# OCP.net
KiCad netlist of a schematic drawn in Altium Designer
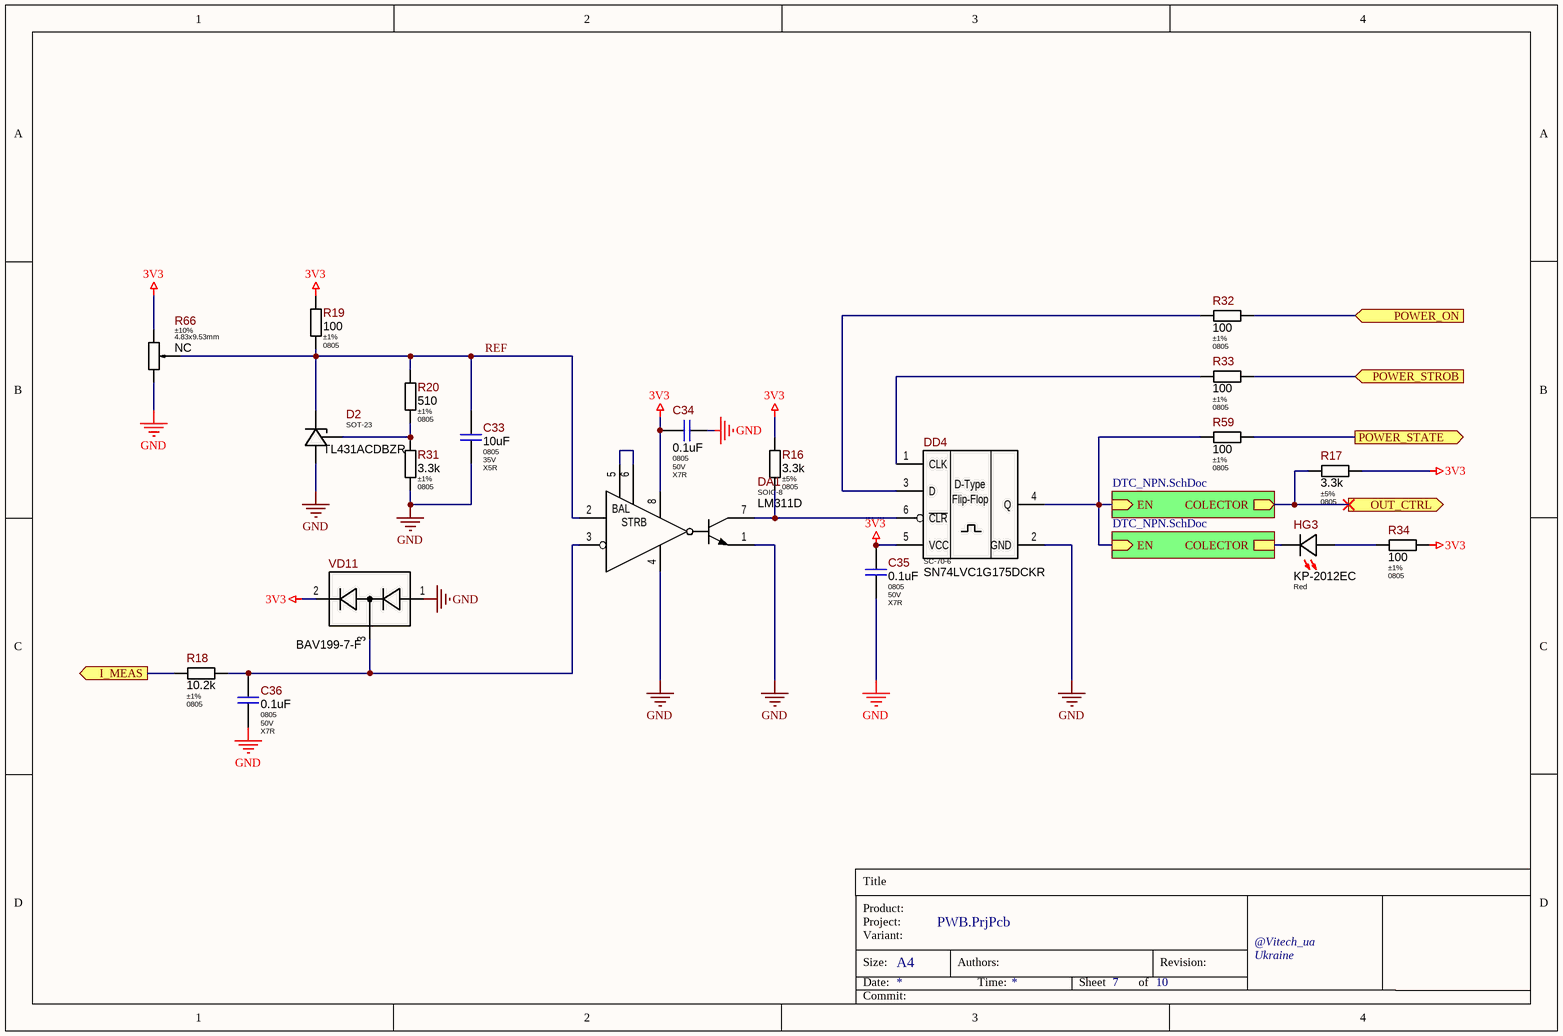
[diagram p0: OCP.SchDoc]

(export (version "E")
  (design (tool "Eeschema 10.0.6"))
  (components
    (comp (ref "C33")
      (value "10uF")
      (footprint "CAP-0805(2012)X125T20")
      (description "10uF 35V X5R ±10% 0805 Low ESL Ceramic Capacitor RoHS")
      (fields
        (field (name "PACKAGE") "0805")
        (field (name "VOLTAGE") "35V")
        (field (name "DIELECTRIC TYPE") "X5R")
        (field (name "PART NUMBER") "C2012X5R1V106K125AC")
        (field (name "MANUFACTURER") "TDK Corporation")
      )
      (libsource (lib "capacitors") (part "C2012X5R1V106K125AC"))
    )
    (comp (ref "C34")
      (value "0.1uF")
      (footprint "CAP-0805(2012)X85T10")
      (description "100nF 50V X7R ±10% 0805 Ceramic Capacitor RoHS")
      (fields
        (field (name "PACKAGE") "0805")
        (field (name "VOLTAGE") "50V")
        (field (name "DIELECTRIC TYPE") "X7R")
        (field (name "PART NUMBER") "CL21B104KBCNNNC")
        (field (name "MANUFACTURER") "Samsung Electro-Mechanics")
      )
      (libsource (lib "capacitors") (part "CL21B104KBCNNNC"))
    )
    (comp (ref "C35")
      (value "0.1uF")
      (footprint "CAP-0805(2012)X85T10")
      (description "100nF 50V X7R ±10% 0805 Ceramic Capacitor RoHS")
      (fields
        (field (name "PACKAGE") "0805")
        (field (name "VOLTAGE") "50V")
        (field (name "DIELECTRIC TYPE") "X7R")
        (field (name "PART NUMBER") "CL21B104KBCNNNC")
        (field (name "MANUFACTURER") "Samsung Electro-Mechanics")
      )
      (libsource (lib "capacitors") (part "CL21B104KBCNNNC"))
    )
    (comp (ref "C36")
      (value "0.1uF")
      (footprint "CAP-0805(2012)X85T10")
      (description "100nF 50V X7R ±10% 0805 Ceramic Capacitor RoHS")
      (fields
        (field (name "PACKAGE") "0805")
        (field (name "VOLTAGE") "50V")
        (field (name "DIELECTRIC TYPE") "X7R")
        (field (name "PART NUMBER") "CL21B104KBCNNNC")
        (field (name "MANUFACTURER") "Samsung Electro-Mechanics")
      )
      (libsource (lib "capacitors") (part "CL21B104KBCNNNC"))
    )
    (comp (ref "D2")
      (value "TL431ACDBZR")
      (footprint "SOT-23_MED")
      (description "Adjustable Precision Shunt Regulator, Accuracy 1%,  SOT-23-3")
      (fields
        (field (name "PACKAGE") "SOT-23")
        (field (name "PART NUMBER") "TL431ACDBZR")
        (field (name "MANUFACTURER") "Texas Instruments")
      )
      (libsource (lib "ic") (part "TL431ACDBZR"))
    )
    (comp (ref "DA1")
      (value "LM311D")
      (footprint "SOIC-8_W3.9MM")
      (description "Differential General Purpose Comparator with Open-Collector, Open-Emitter, SOIC-8")
      (fields
        (field (name "PACKAGE") "SOIC-8")
        (field (name "PART NUMBER") "LM311D")
        (field (name "MANUFACTURER") "Texas Instruments")
      )
      (libsource (lib "ic") (part "LM311D"))
    )
    (comp (ref "DD4")
      (value "SN74LVC1G175DCKR")
      (footprint "SC-70-6")
      (description "Single D-type Flip-Flop with Asynchronous Clear, Positive Edge Trigger, SC-70-6")
      (fields
        (field (name "PACKAGE") "SC-70-6")
        (field (name "PART NUMBER") "SN74LVC1G175DCKR")
        (field (name "MANUFACTURER") "Texas Instruments")
      )
      (libsource (lib "ic") (part "SN74LVC1G175DCKR"))
    )
    (comp (ref "HG3")
      (value "KP-2012EC")
      (footprint "KP-2012EC")
      (description "Low Power LED, Red 617nm, SMD, Vf 2V, 15mcd @ 20 mA, 160°")
      (fields
        (field (name "PART NUMBER") "KP-2012EC")
        (field (name "COLOR") "Red")
        (field (name "MANUFACTURER") "Kingbright")
      )
      (libsource (lib "opto") (part "KP-2012EC"))
    )
    (comp (ref "R16")
      (value "3.3k")
      (footprint "R_ANY_CHIP_0805_MED")
      (description "3.3 kOhms ±5%, 1/8W 0805 Thick Film Resistor")
      (fields
        (field (name "TOLERANCE") "±5%")
        (field (name "PACKAGE") "0805")
        (field (name "PART NUMBER") "RC0805JR-073K3L")
        (field (name "MANUFACTURER") "Yageo")
      )
      (libsource (lib "resistors") (part "RC0805JR-073K3L"))
    )
    (comp (ref "R17")
      (value "3.3k")
      (footprint "R_ANY_CHIP_0805_MED")
      (description "3.3 kOhms ±5%, 1/8W 0805 Thick Film Resistor")
      (fields
        (field (name "TOLERANCE") "±5%")
        (field (name "PACKAGE") "0805")
        (field (name "PART NUMBER") "RC0805JR-073K3L")
        (field (name "MANUFACTURER") "Yageo")
      )
      (libsource (lib "resistors") (part "RC0805JR-073K3L"))
    )
    (comp (ref "R18")
      (value "10.2k")
      (footprint "R_ANY_CHIP_0805_MED")
      (description "10.2 kOhms ±1%, 1/8W 0805 Thick Film Resistor")
      (fields
        (field (name "TOLERANCE") "±1%")
        (field (name "PACKAGE") "0805")
        (field (name "PART NUMBER") "RC0805FR-0710K2L")
        (field (name "MANUFACTURER") "Yageo")
      )
      (libsource (lib "resistors") (part "RC0805FR-0710K2L"))
    )
    (comp (ref "R19")
      (value "100")
      (footprint "R_ANY_CHIP_0805_MED")
      (description "3.3 kOhms ±5%, 1/8W 0805 Thick Film Resistor")
      (fields
        (field (name "TOLERANCE") "±1%")
        (field (name "PACKAGE") "0805")
        (field (name "PART NUMBER") "RC0805JR-07100")
        (field (name "MANUFACTURER") "Yageo")
      )
      (libsource (lib "resistors") (part "RC0805JR-073K3L"))
    )
    (comp (ref "R20")
      (value "510")
      (footprint "R_ANY_CHIP_0805_MED")
      (description "510 Ohms ±5%, 1/8W 0805 Thick Film Resistor")
      (fields
        (field (name "TOLERANCE") "±1%")
        (field (name "PACKAGE") "0805")
        (field (name "PART NUMBER") "CRCW0805510RJNEA")
        (field (name "MANUFACTURER") "Vishay")
      )
      (libsource (lib "resistors") (part "CRCW0805510RJNEA"))
    )
    (comp (ref "R31")
      (value "3.3k")
      (footprint "R_ANY_CHIP_0805_MED")
      (description "3.3 kOhms ±5%, 1/8W 0805 Thick Film Resistor")
      (fields
        (field (name "TOLERANCE") "±1%")
        (field (name "PACKAGE") "0805")
        (field (name "PART NUMBER") "RC0805JR-073K3L")
        (field (name "MANUFACTURER") "Yageo")
      )
      (libsource (lib "resistors") (part "RC0805JR-073K3L"))
    )
    (comp (ref "R32")
      (value "100")
      (footprint "R_ANY_CHIP_0805_MED")
      (description "3.3 kOhms ±5%, 1/8W 0805 Thick Film Resistor")
      (fields
        (field (name "TOLERANCE") "±1%")
        (field (name "PACKAGE") "0805")
        (field (name "PART NUMBER") "RC0805JR-07100")
        (field (name "MANUFACTURER") "Yageo")
      )
      (libsource (lib "resistors") (part "RC0805JR-073K3L"))
    )
    (comp (ref "R33")
      (value "100")
      (footprint "R_ANY_CHIP_0805_MED")
      (description "3.3 kOhms ±5%, 1/8W 0805 Thick Film Resistor")
      (fields
        (field (name "TOLERANCE") "±1%")
        (field (name "PACKAGE") "0805")
        (field (name "PART NUMBER") "RC0805JR-07100")
        (field (name "MANUFACTURER") "Yageo")
      )
      (libsource (lib "resistors") (part "RC0805JR-073K3L"))
    )
    (comp (ref "R34")
      (value "100")
      (footprint "R_ANY_CHIP_0805_MED")
      (description "3.3 kOhms ±5%, 1/8W 0805 Thick Film Resistor")
      (fields
        (field (name "TOLERANCE") "±1%")
        (field (name "PACKAGE") "0805")
        (field (name "PART NUMBER") "RC0805JR-07100")
        (field (name "MANUFACTURER") "Yageo")
      )
      (libsource (lib "resistors") (part "RC0805JR-073K3L"))
    )
    (comp (ref "R59")
      (value "100")
      (footprint "R_ANY_CHIP_0805_MED")
      (description "3.3 kOhms ±5%, 1/8W 0805 Thick Film Resistor")
      (fields
        (field (name "TOLERANCE") "±1%")
        (field (name "PACKAGE") "0805")
        (field (name "PART NUMBER") "RC0805JR-07100")
        (field (name "MANUFACTURER") "Yageo")
      )
      (libsource (lib "resistors") (part "RC0805JR-073K3L"))
    )
    (comp (ref "R66")
      (value "NC")
      (footprint "3296W-1-xxx")
      (description "10 kOhms ±10% Trimmer Resistor, 0.5W, Through Hole 3/8\", 4.83x9.53mm, 10.03mm Height")
      (fields
        (field (name "TOLERANCE") "±10%")
        (field (name "PACKAGE") "4.83x9.53mm")
        (field (name "PART NUMBER") "3296W-1-103LF")
        (field (name "MANUFACTURER") "Bourns")
      )
      (libsource (lib "resistors") (part "3296W-1-103LF"))
    )
    (comp (ref "VD11")
      (value "BAV199-7-F")
      (footprint "SOT-23_MED")
      (description "Diode Array 1 Pair Series Connection Standard 85V 160mA, 5nA Reverse Current, SOT-23")
      (fields
        (field (name "VOLTAGE") "85V")
        (field (name "PART NUMBER") "BAV199-7-F")
        (field (name "MANUFACTURER") "Diodes Incorporated")
      )
      (libsource (lib "diodes") (part "BAV199-7-F"))
    )
  )
  (nets
    (net (code "1") (name "/COLECTOR") (class "Default")
      (node (ref "HG3") (pin "CA") (pinfunction "Cathode_CA") (pintype "passive"))
    )
    (net (code "2") (name "/EN") (class "Default")
      (node (ref "DD4") (pin "4") (pinfunction "Q_4") (pintype "passive"))
      (node (ref "R59") (pin "1") (pintype "passive"))
    )
    (net (code "3") (name "/I_MEAS") (class "Default") (node (ref "R18") (pin "2") (pintype "passive")))
    (net (code "4") (name "/OUT_CTRL") (class "Default")
      (node (ref "R17") (pin "2") (pintype "passive+no_connect"))
    )
    (net (code "5") (name "/POWER_ON") (class "Default") (node (ref "R32") (pin "2") (pintype "passive")))
    (net (code "6") (name "/POWER_STATE") (class "Default") (node (ref "R59") (pin "2") (pintype "passive")))
    (net (code "7") (name "/POWER_STROB") (class "Default") (node (ref "R33") (pin "2") (pintype "passive")))
    (net (code "8") (name "/REF") (class "Default")
      (node (ref "C33") (pin "1") (pinfunction "1_1") (pintype "passive"))
      (node (ref "D2") (pin "1") (pinfunction "C_1") (pintype "passive"))
      (node (ref "DA1") (pin "2") (pinfunction "IN+_2") (pintype "passive"))
      (node (ref "R19") (pin "2") (pintype "passive"))
      (node (ref "R20") (pin "1") (pintype "passive"))
      (node (ref "R66") (pin "2") (pinfunction "WIPER_2") (pintype "passive"))
    )
    (net (code "9") (name "3V3") (class "Default")
      (node (ref "C34") (pin "1") (pinfunction "1_1") (pintype "passive"))
      (node (ref "C35") (pin "1") (pinfunction "1_1") (pintype "passive"))
      (node (ref "DA1") (pin "8") (pinfunction "VCC_8") (pintype "passive"))
      (node (ref "DD4") (pin "5") (pinfunction "VCC_5") (pintype "passive"))
      (node (ref "R16") (pin "1") (pintype "passive"))
      (node (ref "R17") (pin "1") (pintype "passive"))
      (node (ref "R19") (pin "1") (pintype "passive"))
      (node (ref "R34") (pin "2") (pintype "passive"))
      (node (ref "R66") (pin "1") (pinfunction "CCW_1") (pintype "passive"))
      (node (ref "VD11") (pin "2") (pintype "passive"))
    )
    (net (code "10") (name "GND") (class "Default")
      (node (ref "C33") (pin "2") (pinfunction "2_2") (pintype "passive"))
      (node (ref "C34") (pin "2") (pinfunction "2_2") (pintype "passive"))
      (node (ref "C35") (pin "2") (pinfunction "2_2") (pintype "passive"))
      (node (ref "C36") (pin "2") (pinfunction "2_2") (pintype "passive"))
      (node (ref "D2") (pin "3") (pinfunction "A_3") (pintype "passive"))
      (node (ref "DA1") (pin "1") (pinfunction "EMIT_OUT_1") (pintype "passive"))
      (node (ref "DA1") (pin "4") (pinfunction "GND_4") (pintype "passive"))
      (node (ref "DD4") (pin "2") (pinfunction "GND_2") (pintype "passive"))
      (node (ref "R31") (pin "2") (pintype "passive"))
      (node (ref "R66") (pin "3") (pinfunction "CW_3") (pintype "passive"))
      (node (ref "VD11") (pin "1") (pintype "passive"))
    )
    (net (code "11") (name "Net-(D2-REF)") (class "Default")
      (node (ref "D2") (pin "2") (pinfunction "REF_2") (pintype "passive"))
      (node (ref "R20") (pin "2") (pintype "passive"))
      (node (ref "R31") (pin "1") (pintype "passive"))
    )
    (net (code "12") (name "Net-(DA1-BALANCE)") (class "Default")
      (node (ref "DA1") (pin "5") (pinfunction "BALANCE_5") (pintype "passive"))
      (node (ref "DA1") (pin "6") (pinfunction "BAL/STRB_6") (pintype "passive"))
    )
    (net (code "13") (name "Net-(DA1-COL_OUT)") (class "Default")
      (node (ref "DA1") (pin "7") (pinfunction "COL_OUT_7") (pintype "passive"))
      (node (ref "DD4") (pin "6") (pinfunction "~{CLR}_6") (pintype "passive"))
      (node (ref "R16") (pin "2") (pintype "passive"))
    )
    (net (code "14") (name "Net-(DA1-IN-)") (class "Default")
      (node (ref "C36") (pin "1") (pinfunction "1_1") (pintype "passive"))
      (node (ref "DA1") (pin "3") (pinfunction "IN-_3") (pintype "passive"))
      (node (ref "R18") (pin "1") (pintype "passive"))
      (node (ref "VD11") (pin "3") (pintype "passive"))
    )
    (net (code "15") (name "Net-(DD4-CLK)") (class "Default")
      (node (ref "DD4") (pin "1") (pinfunction "CLK_1") (pintype "passive"))
      (node (ref "R33") (pin "1") (pintype "passive"))
    )
    (net (code "16") (name "Net-(DD4-D)") (class "Default")
      (node (ref "DD4") (pin "3") (pinfunction "D_3") (pintype "passive"))
      (node (ref "R32") (pin "1") (pintype "passive"))
    )
    (net (code "17") (name "Net-(HG3-Anode)") (class "Default")
      (node (ref "HG3") (pin "AN") (pinfunction "Anode_AN") (pintype "passive"))
      (node (ref "R34") (pin "1") (pintype "passive"))
    )
  )
)
